# MCU_Control.net
KiCad netlist of a schematic drawn in Altium Designer
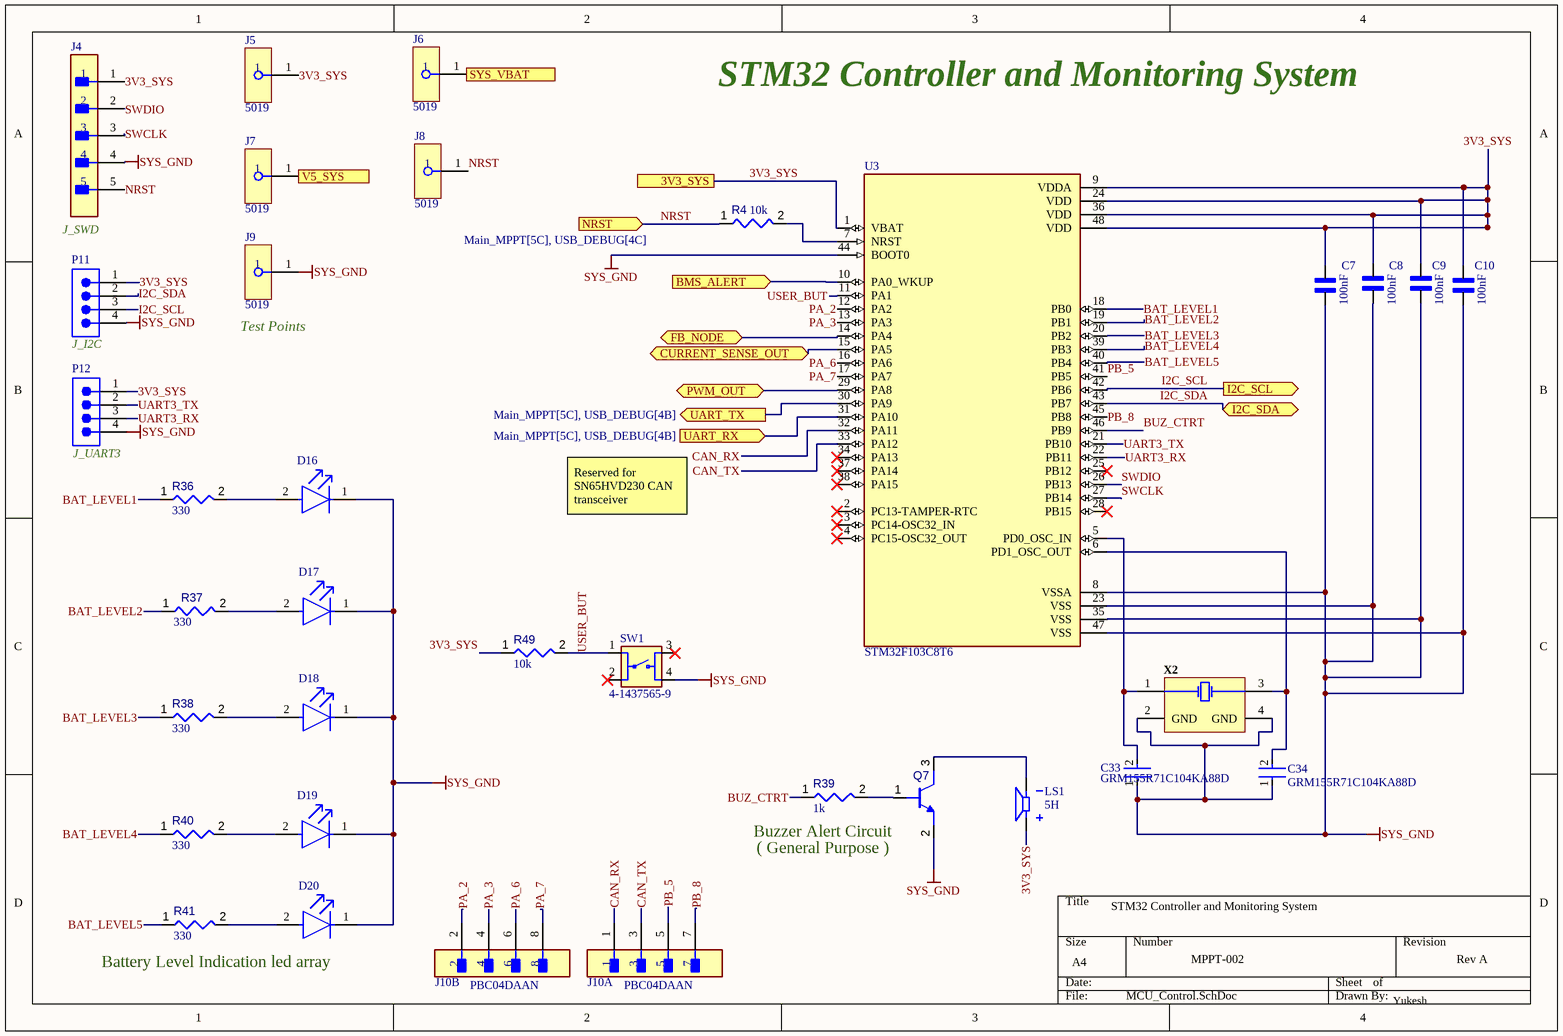
[diagram p0: MCU_Control.SchDoc]

(export (version "E")
  (design (tool "Eeschema 10.0.6"))
  (components
    (comp (ref "C7")
      (value "100nF")
      (footprint "CAPC1608X90N")
      (description "Capacitor MLCC 0603 100nF 16V")
      (fields (field (name "MP") "0603YC104KAZ2A") (field (name "MF") "AVX"))
      (libsource (lib "YUKESH S") (part "0603YC104KAZ2A"))
    )
    (comp (ref "C8")
      (value "100nF")
      (footprint "CAPC1608X90N")
      (description "Capacitor MLCC 0603 100nF 16V")
      (fields (field (name "MP") "0603YC104KAZ2A") (field (name "MF") "AVX"))
      (libsource (lib "YUKESH S") (part "0603YC104KAZ2A"))
    )
    (comp (ref "C9")
      (value "100nF")
      (footprint "CAPC1608X90N")
      (description "Capacitor MLCC 0603 100nF 16V")
      (fields (field (name "MP") "0603YC104KAZ2A") (field (name "MF") "AVX"))
      (libsource (lib "YUKESH S") (part "0603YC104KAZ2A"))
    )
    (comp (ref "C10")
      (value "100nF")
      (footprint "CAPC1608X90N")
      (description "Capacitor MLCC 0603 100nF 16V")
      (fields (field (name "MP") "0603YC104KAZ2A") (field (name "MF") "AVX"))
      (libsource (lib "YUKESH S") (part "0603YC104KAZ2A"))
    )
    (comp (ref "C33")
      (value "GRM155R71C104KA88D")
      (footprint "FP-GRM15-MFG")
      (description "CAP CER 0.1UF 16V X7R 0402")
      (fields
        (field (name "TOLERANCE") "10%")
        (field (name "OCTOPART") "https://octopart.com/grm155r71c104ka88d-murata-196880")
      )
      (libsource (lib "Altium Content Vault") (part "236180d848d6139a670b325ea6854c9"))
    )
    (comp (ref "C34")
      (value "GRM155R71C104KA88D")
      (footprint "FP-GRM15-MFG")
      (description "CAP CER 0.1UF 16V X7R 0402")
      (fields
        (field (name "TOLERANCE") "10%")
        (field (name "OCTOPART") "https://octopart.com/grm155r71c104ka88d-murata-196880")
      )
      (libsource (lib "Altium Content Vault") (part "236180d848d6139a670b325ea6854c9"))
    )
    (comp (ref "D16")
      (value "SML-LX0805UWC-TR")
      (footprint "FP-SML-LX0805UWC-TR-MFG")
      (description "SML-LX0805UWC-TR White LED, 0805 Diffused, Rectangle Lens SMD package")
      (libsource (lib "Altium Content Vault") (part "8706943c75ba83719d021d2fdc84c58"))
    )
    (comp (ref "D17")
      (value "SML-LX0805UWC-TR")
      (footprint "FP-SML-LX0805UWC-TR-MFG")
      (description "SML-LX0805UWC-TR White LED, 0805 Diffused, Rectangle Lens SMD package")
      (libsource (lib "Altium Content Vault") (part "8706943c75ba83719d021d2fdc84c58"))
    )
    (comp (ref "D18")
      (value "SML-LX0805UWC-TR")
      (footprint "FP-SML-LX0805UWC-TR-MFG")
      (description "SML-LX0805UWC-TR White LED, 0805 Diffused, Rectangle Lens SMD package")
      (libsource (lib "Altium Content Vault") (part "8706943c75ba83719d021d2fdc84c58"))
    )
    (comp (ref "D19")
      (value "SML-LX0805UWC-TR")
      (footprint "FP-SML-LX0805UWC-TR-MFG")
      (description "SML-LX0805UWC-TR White LED, 0805 Diffused, Rectangle Lens SMD package")
      (libsource (lib "Altium Content Vault") (part "8706943c75ba83719d021d2fdc84c58"))
    )
    (comp (ref "D20")
      (value "SML-LX0805UWC-TR")
      (footprint "FP-SML-LX0805UWC-TR-MFG")
      (description "SML-LX0805UWC-TR White LED, 0805 Diffused, Rectangle Lens SMD package")
      (libsource (lib "Altium Content Vault") (part "8706943c75ba83719d021d2fdc84c58"))
    )
    (comp (ref "J4")
      (value "22-28-4050")
      (footprint "FP-22-28-4050-MFG")
      (libsource (lib "Altium Content Vault") (part "bf93c07fd2649a848d0ec8585582aab"))
    )
    (comp (ref "J5")
      (value "5019")
      (footprint "5019_MFG")
      (description "Phosphor Bronze Contact Miniature Silver Plated Surface Mount Test Points")
      (libsource (lib "Altium Content Vault") (part "2b5a64f1d553f7b761d27cd6d0c3a70"))
    )
    (comp (ref "J6")
      (value "5019")
      (footprint "5019_MFG")
      (description "Phosphor Bronze Contact Miniature Silver Plated Surface Mount Test Points")
      (libsource (lib "Altium Content Vault") (part "2b5a64f1d553f7b761d27cd6d0c3a70"))
    )
    (comp (ref "J7")
      (value "5019")
      (footprint "5019_MFG")
      (description "Phosphor Bronze Contact Miniature Silver Plated Surface Mount Test Points")
      (libsource (lib "Altium Content Vault") (part "2b5a64f1d553f7b761d27cd6d0c3a70"))
    )
    (comp (ref "J8")
      (value "5019")
      (footprint "5019_MFG")
      (description "Phosphor Bronze Contact Miniature Silver Plated Surface Mount Test Points")
      (libsource (lib "Altium Content Vault") (part "2b5a64f1d553f7b761d27cd6d0c3a70"))
    )
    (comp (ref "J9")
      (value "5019")
      (footprint "5019_MFG")
      (description "Phosphor Bronze Contact Miniature Silver Plated Surface Mount Test Points")
      (libsource (lib "Altium Content Vault") (part "2b5a64f1d553f7b761d27cd6d0c3a70"))
    )
    (comp (ref "J10")
      (value "PBC04DAAN")
      (footprint "FP-PBC04DAAN-MFG")
      (description "CONN HEADER VERT 8POS 2.54MM")
      (libsource (lib "Altium Content Vault") (part "811e954b9c034aa737de4d9295cbe7e"))
    )
    (comp (ref "LS1")
      (value "5H")
      (footprint "XDCR_CMI-1210-5-95T")
      (description "12 mm, 5 Vdc, 98 dB, Through Hole, Magnetic Audio Indicator Buzzer")
      (fields (field (name "MF") "Same Sky") (field (name "MP") "CMI-1210-5-95T"))
      (libsource (lib "YUKESH S") (part "CMI-1210-5-95T"))
    )
    (comp (ref "P11")
      (value "TSW-104-08-G-S")
      (footprint "SMTC-TSW-104-08-X-S")
      (description "0.025\" SQ Post Header, Through-hole, Vertical, -55 to 125 degC, 2.54 mm Pitch, 4-Pin, Male, RoHS")
      (fields (field (name "MANUFACTURER") "Samtec"))
      (libsource (lib "Altium Content Vault") (part "SMTC-TSW-104-08-X-S"))
    )
    (comp (ref "P12")
      (value "TSW-104-08-G-S")
      (footprint "SMTC-TSW-104-08-X-S")
      (description "0.025\" SQ Post Header, Through-hole, Vertical, -55 to 125 degC, 2.54 mm Pitch, 4-Pin, Male, RoHS")
      (fields (field (name "MANUFACTURER") "Samtec"))
      (libsource (lib "Altium Content Vault") (part "SMTC-TSW-104-08-X-S"))
    )
    (comp (ref "Q7")
      (value "MMBT2222AM3T5G")
      (footprint "ROHM-SOT723-3_V")
      (description "NPN General Purpose Transistor, 3-Pin SOT-723, Pb-Free, Tape and Reel")
      (libsource (lib "YUKESH S") (part "CMP-00026-6"))
    )
    (comp (ref "R4")
      (value "10k")
      (footprint "RESC3216X60X45ML15T20")
      (description "Chip Resistor, 10 KOhm, +/- 1%, 0.25 W, -55 to 155 degC, 1206 (3216 Metric)")
      (fields (field (name "TOLERANCE") "1%") (field (name "POWER") "250mW"))
      (libsource (lib "YUKESH S") (part "RES-2"))
    )
    (comp (ref "R36")
      (value "330")
      (footprint "RESC0402(1005)_L")
      (description "330R 0.063W 5% 0402 (1005 Metric)  SMD")
      (fields (field (name "TOLERANCE") "5%") (field (name "POWER") "63mW"))
      (libsource (lib "YUKESH S") (part "330R2J"))
    )
    (comp (ref "R37")
      (value "330")
      (footprint "RESC0402(1005)_L")
      (description "330R 0.063W 5% 0402 (1005 Metric)  SMD")
      (fields (field (name "TOLERANCE") "5%") (field (name "POWER") "63mW"))
      (libsource (lib "YUKESH S") (part "330R2J"))
    )
    (comp (ref "R38")
      (value "330")
      (footprint "RESC0402(1005)_L")
      (description "330R 0.063W 5% 0402 (1005 Metric)  SMD")
      (fields (field (name "TOLERANCE") "5%") (field (name "POWER") "63mW"))
      (libsource (lib "YUKESH S") (part "330R2J"))
    )
    (comp (ref "R39")
      (value "1k")
      (footprint "RESC0805(2012)_L")
      (description "1K 0.125W 5% 0805 (2012 Metric)  SMD")
      (fields (field (name "TOLERANCE") "5%") (field (name "POWER") "125mW"))
      (libsource (lib "YUKESH S") (part "1KR5J"))
    )
    (comp (ref "R40")
      (value "330")
      (footprint "RESC0402(1005)_L")
      (description "330R 0.063W 5% 0402 (1005 Metric)  SMD")
      (fields (field (name "TOLERANCE") "5%") (field (name "POWER") "63mW"))
      (libsource (lib "YUKESH S") (part "330R2J"))
    )
    (comp (ref "R41")
      (value "330")
      (footprint "RESC0402(1005)_L")
      (description "330R 0.063W 5% 0402 (1005 Metric)  SMD")
      (fields (field (name "TOLERANCE") "5%") (field (name "POWER") "63mW"))
      (libsource (lib "YUKESH S") (part "330R2J"))
    )
    (comp (ref "R49")
      (value "10k")
      (footprint "RESC0402(1005)_L")
      (description "10K 0.063W 1% 0402 (1005 Metric)  SMD")
      (fields (field (name "POWER") "63mW") (field (name "TOLERANCE") "1%"))
      (libsource (lib "YUKESH S") (part "10KR2F"))
    )
    (comp (ref "SW1")
      (value "4-1437565-9")
      (footprint "TE_4-1437565-9")
      (description "Alcoswitch, Switch, Tactile, 50 mA, SPST, Pushbutton, Off[On], FSM6JSMA")
      (fields (field (name "MF") "TE Connectivity") (field (name "MP") "FSM6JSMA"))
      (libsource (lib "YUKESH S") (part "4-1437565-9"))
    )
    (comp (ref "U3")
      (value "STM32F103C8T6")
      (footprint "QFP50P900X900X160-48N")
      (description "ARM® Cortex®-M3 STM32F1 Microcontroller IC 32-Bit 72MHz 64KB (64K x 8) FLASH 48-LQFP (7x7)")
      (fields (field (name "MF") "STMicroelectronics"))
      (libsource (lib "YUKESH S") (part "STM32F103C8T6"))
    )
    (comp (ref "X2")
      (value "TSX-3225 24.0000MF15X-AC3")
      (footprint "EPSON-TSX-3225_V")
      (description "MHz Range Crystal, 24 MHz, -40 to 85 degC, 4-Pin SMD, RoHS, Tape and Reel")
      (fields (field (name "TOLERANCE") "10PPM") (field (name "MANUFACTURER") "Epson"))
      (libsource (lib "Altium Content Vault") (part "XTAL-1-3-4"))
    )
  )
  (nets
    (net (code "1") (name "/3V3_SYS") (class "Default")
      (node (ref "C10") (pin "2") (pinfunction "2_2") (pintype "passive"))
      (node (ref "C7") (pin "2") (pinfunction "2_2") (pintype "passive"))
      (node (ref "C8") (pin "2") (pinfunction "2_2") (pintype "passive"))
      (node (ref "C9") (pin "2") (pinfunction "2_2") (pintype "passive"))
      (node (ref "J4") (pin "1") (pinfunction "1_1") (pintype "passive"))
      (node (ref "J5") (pin "1") (pinfunction "1_1") (pintype "passive"))
      (node (ref "LS1") (pin "P") (pinfunction "P_P") (pintype "passive"))
      (node (ref "P11") (pin "1") (pinfunction "1_1") (pintype "passive"))
      (node (ref "P12") (pin "1") (pinfunction "1_1") (pintype "passive"))
      (node (ref "R49") (pin "1") (pinfunction "1_1") (pintype "passive"))
      (node (ref "U3") (pin "1") (pinfunction "VBAT_1") (pintype "bidirectional"))
      (node (ref "U3") (pin "24") (pinfunction "VDD_24") (pintype "power_in"))
      (node (ref "U3") (pin "36") (pinfunction "VDD_36") (pintype "power_in"))
      (node (ref "U3") (pin "48") (pinfunction "VDD_48") (pintype "power_in"))
      (node (ref "U3") (pin "9") (pinfunction "VDDA_9") (pintype "power_in"))
    )
    (net (code "2") (name "/BAT_LEVEL1") (class "Default")
      (node (ref "R36") (pin "1") (pinfunction "1_1") (pintype "passive"))
      (node (ref "U3") (pin "18") (pinfunction "PB0_18") (pintype "bidirectional"))
    )
    (net (code "3") (name "/BAT_LEVEL2") (class "Default")
      (node (ref "R37") (pin "1") (pinfunction "1_1") (pintype "passive"))
      (node (ref "U3") (pin "19") (pinfunction "PB1_19") (pintype "bidirectional"))
    )
    (net (code "4") (name "/BAT_LEVEL3") (class "Default")
      (node (ref "R38") (pin "1") (pinfunction "1_1") (pintype "passive"))
      (node (ref "U3") (pin "20") (pinfunction "PB2_20") (pintype "bidirectional"))
    )
    (net (code "5") (name "/BAT_LEVEL4") (class "Default")
      (node (ref "R40") (pin "1") (pinfunction "1_1") (pintype "passive"))
      (node (ref "U3") (pin "39") (pinfunction "PB3_39") (pintype "bidirectional"))
    )
    (net (code "6") (name "/BAT_LEVEL5") (class "Default")
      (node (ref "R41") (pin "1") (pinfunction "1_1") (pintype "passive"))
      (node (ref "U3") (pin "40") (pinfunction "PB4_40") (pintype "bidirectional"))
    )
    (net (code "7") (name "/BMS_ALERT") (class "Default")
      (node (ref "U3") (pin "10") (pinfunction "PA0_WKUP_10") (pintype "bidirectional"))
    )
    (net (code "8") (name "/BUZ_CTRT") (class "Default")
      (node (ref "R39") (pin "1") (pinfunction "1_1") (pintype "passive"))
      (node (ref "U3") (pin "46") (pinfunction "PB9_46") (pintype "bidirectional"))
    )
    (net (code "9") (name "/CAN_RX") (class "Default")
      (node (ref "J10") (pin "1") (pinfunction "1_1") (pintype "passive"))
      (node (ref "U3") (pin "32") (pinfunction "PA11_32") (pintype "bidirectional"))
    )
    (net (code "10") (name "/CAN_TX") (class "Default")
      (node (ref "J10") (pin "3") (pinfunction "3_3") (pintype "passive"))
      (node (ref "U3") (pin "33") (pinfunction "PA12_33") (pintype "bidirectional"))
    )
    (net (code "11") (name "/CURRENT_SENSE_OUT") (class "Default")
      (node (ref "U3") (pin "15") (pinfunction "PA5_15") (pintype "bidirectional"))
    )
    (net (code "12") (name "/FB_NODE") (class "Default")
      (node (ref "U3") (pin "14") (pinfunction "PA4_14") (pintype "bidirectional"))
    )
    (net (code "13") (name "/I2C_SCL") (class "Default")
      (node (ref "P11") (pin "3") (pinfunction "3_3") (pintype "passive"))
      (node (ref "U3") (pin "42") (pinfunction "PB6_42") (pintype "bidirectional"))
    )
    (net (code "14") (name "/I2C_SDA") (class "Default")
      (node (ref "P11") (pin "2") (pinfunction "2_2") (pintype "passive"))
      (node (ref "U3") (pin "43") (pinfunction "PB7_43") (pintype "bidirectional"))
    )
    (net (code "15") (name "/NRST") (class "Default")
      (node (ref "J4") (pin "5") (pinfunction "5_5") (pintype "passive"))
      (node (ref "J8") (pin "1") (pinfunction "1_1") (pintype "passive"))
      (node (ref "R4") (pin "1") (pinfunction "1_1") (pintype "passive"))
    )
    (net (code "16") (name "/PA_2") (class "Default")
      (node (ref "J10") (pin "2") (pinfunction "2_2") (pintype "passive"))
      (node (ref "U3") (pin "12") (pinfunction "PA2_12") (pintype "bidirectional"))
    )
    (net (code "17") (name "/PA_3") (class "Default")
      (node (ref "J10") (pin "4") (pinfunction "4_4") (pintype "passive"))
      (node (ref "U3") (pin "13") (pinfunction "PA3_13") (pintype "bidirectional"))
    )
    (net (code "18") (name "/PA_6") (class "Default")
      (node (ref "J10") (pin "6") (pinfunction "6_6") (pintype "passive"))
      (node (ref "U3") (pin "16") (pinfunction "PA6_16") (pintype "bidirectional"))
    )
    (net (code "19") (name "/PA_7") (class "Default")
      (node (ref "J10") (pin "8") (pinfunction "8_8") (pintype "passive"))
      (node (ref "U3") (pin "17") (pinfunction "PA7_17") (pintype "bidirectional"))
    )
    (net (code "20") (name "/PB_5") (class "Default")
      (node (ref "J10") (pin "5") (pinfunction "5_5") (pintype "passive"))
      (node (ref "U3") (pin "41") (pinfunction "PB5_41") (pintype "bidirectional"))
    )
    (net (code "21") (name "/PB_8") (class "Default")
      (node (ref "J10") (pin "7") (pinfunction "7_7") (pintype "passive"))
      (node (ref "U3") (pin "45") (pinfunction "PB8_45") (pintype "bidirectional"))
    )
    (net (code "22") (name "/PWM_OUT") (class "Default")
      (node (ref "U3") (pin "29") (pinfunction "PA8_29") (pintype "bidirectional"))
    )
    (net (code "23") (name "/SWCLK") (class "Default")
      (node (ref "J4") (pin "3") (pinfunction "3_3") (pintype "passive"))
      (node (ref "U3") (pin "27") (pinfunction "PB14_27") (pintype "bidirectional"))
    )
    (net (code "24") (name "/SWDIO") (class "Default")
      (node (ref "J4") (pin "2") (pinfunction "2_2") (pintype "passive"))
      (node (ref "U3") (pin "26") (pinfunction "PB13_26") (pintype "bidirectional"))
    )
    (net (code "25") (name "/SYS_VBAT") (class "Default")
      (node (ref "J6") (pin "1") (pinfunction "1_1") (pintype "passive"))
    )
    (net (code "26") (name "/UART3_RX") (class "Default")
      (node (ref "P12") (pin "3") (pinfunction "3_3") (pintype "passive"))
      (node (ref "U3") (pin "22") (pinfunction "PB11_22") (pintype "bidirectional"))
    )
    (net (code "27") (name "/UART3_TX") (class "Default")
      (node (ref "P12") (pin "2") (pinfunction "2_2") (pintype "passive"))
      (node (ref "U3") (pin "21") (pinfunction "PB10_21") (pintype "bidirectional"))
    )
    (net (code "28") (name "/UART_RX") (class "Default")
      (node (ref "U3") (pin "31") (pinfunction "PA10_31") (pintype "bidirectional"))
    )
    (net (code "29") (name "/UART_TX") (class "Default")
      (node (ref "U3") (pin "30") (pinfunction "PA9_30") (pintype "bidirectional"))
    )
    (net (code "30") (name "/USER_BUT") (class "Default")
      (node (ref "R49") (pin "2") (pinfunction "2_2") (pintype "passive"))
      (node (ref "SW1") (pin "1") (pinfunction "1_1") (pintype "passive"))
      (node (ref "U3") (pin "11") (pinfunction "PA1_11") (pintype "bidirectional"))
    )
    (net (code "31") (name "/V5_SYS") (class "Default")
      (node (ref "J7") (pin "1") (pinfunction "1_1") (pintype "passive"))
    )
    (net (code "32") (name "Net-(D16-A)") (class "Default")
      (node (ref "D16") (pin "2") (pinfunction "A_2") (pintype "passive"))
      (node (ref "R36") (pin "2") (pinfunction "2_2") (pintype "passive"))
    )
    (net (code "33") (name "Net-(D17-A)") (class "Default")
      (node (ref "D17") (pin "2") (pinfunction "A_2") (pintype "passive"))
      (node (ref "R37") (pin "2") (pinfunction "2_2") (pintype "passive"))
    )
    (net (code "34") (name "Net-(D18-A)") (class "Default")
      (node (ref "D18") (pin "2") (pinfunction "A_2") (pintype "passive"))
      (node (ref "R38") (pin "2") (pinfunction "2_2") (pintype "passive"))
    )
    (net (code "35") (name "Net-(D19-A)") (class "Default")
      (node (ref "D19") (pin "2") (pinfunction "A_2") (pintype "passive"))
      (node (ref "R40") (pin "2") (pinfunction "2_2") (pintype "passive"))
    )
    (net (code "36") (name "Net-(D20-A)") (class "Default")
      (node (ref "D20") (pin "2") (pinfunction "A_2") (pintype "passive"))
      (node (ref "R41") (pin "2") (pinfunction "2_2") (pintype "passive"))
    )
    (net (code "37") (name "Net-(Q7-B)") (class "Default")
      (node (ref "Q7") (pin "1") (pinfunction "B_1") (pintype "passive"))
      (node (ref "R39") (pin "2") (pinfunction "2_2") (pintype "passive"))
    )
    (net (code "38") (name "Net-(Q7-C)") (class "Default")
      (node (ref "LS1") (pin "N") (pinfunction "N_N") (pintype "passive"))
      (node (ref "Q7") (pin "3") (pinfunction "C_3") (pintype "passive"))
    )
    (net (code "39") (name "Net-(U3-NRST)") (class "Default")
      (node (ref "R4") (pin "2") (pinfunction "2_2") (pintype "passive"))
      (node (ref "U3") (pin "7") (pinfunction "NRST_7") (pintype "input"))
    )
    (net (code "40") (name "Net-(U3-PD0_OSC_IN)") (class "Default")
      (node (ref "C33") (pin "2") (pinfunction "2_2") (pintype "passive"))
      (node (ref "U3") (pin "5") (pinfunction "PD0_OSC_IN_5") (pintype "bidirectional"))
      (node (ref "X2") (pin "1") (pinfunction "X1_1") (pintype "passive"))
    )
    (net (code "41") (name "Net-(U3-PD1_OSC_OUT)") (class "Default")
      (node (ref "C34") (pin "2") (pinfunction "2_2") (pintype "passive"))
      (node (ref "U3") (pin "6") (pinfunction "PD1_OSC_OUT_6") (pintype "bidirectional"))
      (node (ref "X2") (pin "3") (pinfunction "X2_3") (pintype "passive"))
    )
    (net (code "42") (name "SYS_GND") (class "Default")
      (node (ref "C10") (pin "1") (pinfunction "1_1") (pintype "passive"))
      (node (ref "C33") (pin "1") (pinfunction "1_1") (pintype "passive"))
      (node (ref "C34") (pin "1") (pinfunction "1_1") (pintype "passive"))
      (node (ref "C7") (pin "1") (pinfunction "1_1") (pintype "passive"))
      (node (ref "C8") (pin "1") (pinfunction "1_1") (pintype "passive"))
      (node (ref "C9") (pin "1") (pinfunction "1_1") (pintype "passive"))
      (node (ref "D16") (pin "1") (pinfunction "C_1") (pintype "passive"))
      (node (ref "D17") (pin "1") (pinfunction "C_1") (pintype "passive"))
      (node (ref "D18") (pin "1") (pinfunction "C_1") (pintype "passive"))
      (node (ref "D19") (pin "1") (pinfunction "C_1") (pintype "passive"))
      (node (ref "D20") (pin "1") (pinfunction "C_1") (pintype "passive"))
      (node (ref "J4") (pin "4") (pinfunction "4_4") (pintype "passive"))
      (node (ref "J9") (pin "1") (pinfunction "1_1") (pintype "passive"))
      (node (ref "P11") (pin "4") (pinfunction "4_4") (pintype "passive"))
      (node (ref "P12") (pin "4") (pinfunction "4_4") (pintype "passive"))
      (node (ref "Q7") (pin "2") (pinfunction "E_2") (pintype "passive"))
      (node (ref "SW1") (pin "4") (pinfunction "4_4") (pintype "passive"))
      (node (ref "U3") (pin "23") (pinfunction "VSS_23") (pintype "power_in"))
      (node (ref "U3") (pin "35") (pinfunction "VSS_35") (pintype "power_in"))
      (node (ref "U3") (pin "44") (pinfunction "BOOT0_44") (pintype "input"))
      (node (ref "U3") (pin "47") (pinfunction "VSS_47") (pintype "power_in"))
      (node (ref "U3") (pin "8") (pinfunction "VSSA_8") (pintype "power_in"))
      (node (ref "X2") (pin "2") (pinfunction "GND_2") (pintype "power_in"))
      (node (ref "X2") (pin "4") (pinfunction "GND_4") (pintype "power_in"))
    )
    (net (code "43") (name "unconnected-(SW1-Pad2)") (class "Default")
      (node (ref "SW1") (pin "2") (pinfunction "2_2") (pintype "passive+no_connect"))
    )
    (net (code "44") (name "unconnected-(SW1-Pad3)") (class "Default")
      (node (ref "SW1") (pin "3") (pinfunction "3_3") (pintype "passive+no_connect"))
    )
    (net (code "45") (name "unconnected-(U3-PA13-Pad34)") (class "Default")
      (node (ref "U3") (pin "34") (pinfunction "PA13_34") (pintype "bidirectional+no_connect"))
    )
    (net (code "46") (name "unconnected-(U3-PA14-Pad37)") (class "Default")
      (node (ref "U3") (pin "37") (pinfunction "PA14_37") (pintype "bidirectional+no_connect"))
    )
    (net (code "47") (name "unconnected-(U3-PA15-Pad38)") (class "Default")
      (node (ref "U3") (pin "38") (pinfunction "PA15_38") (pintype "bidirectional+no_connect"))
    )
    (net (code "48") (name "unconnected-(U3-PB12-Pad25)") (class "Default")
      (node (ref "U3") (pin "25") (pinfunction "PB12_25") (pintype "bidirectional+no_connect"))
    )
    (net (code "49") (name "unconnected-(U3-PB15-Pad28)") (class "Default")
      (node (ref "U3") (pin "28") (pinfunction "PB15_28") (pintype "bidirectional+no_connect"))
    )
    (net (code "50") (name "unconnected-(U3-PC13-TAMPER-RTC-Pad2)") (class "Default")
      (node (ref "U3") (pin "2") (pinfunction "PC13-TAMPER-RTC_2") (pintype "bidirectional+no_connect"))
    )
    (net (code "51") (name "unconnected-(U3-PC14-OSC32_IN-Pad3)") (class "Default")
      (node (ref "U3") (pin "3") (pinfunction "PC14-OSC32_IN_3") (pintype "bidirectional+no_connect"))
    )
    (net (code "52") (name "unconnected-(U3-PC15-OSC32_OUT-Pad4)") (class "Default")
      (node (ref "U3") (pin "4") (pinfunction "PC15-OSC32_OUT_4") (pintype "bidirectional+no_connect"))
    )
  )
)
